# Analog_temperature_sensor.net
KiCad netlist of a schematic drawn in Altium Designer
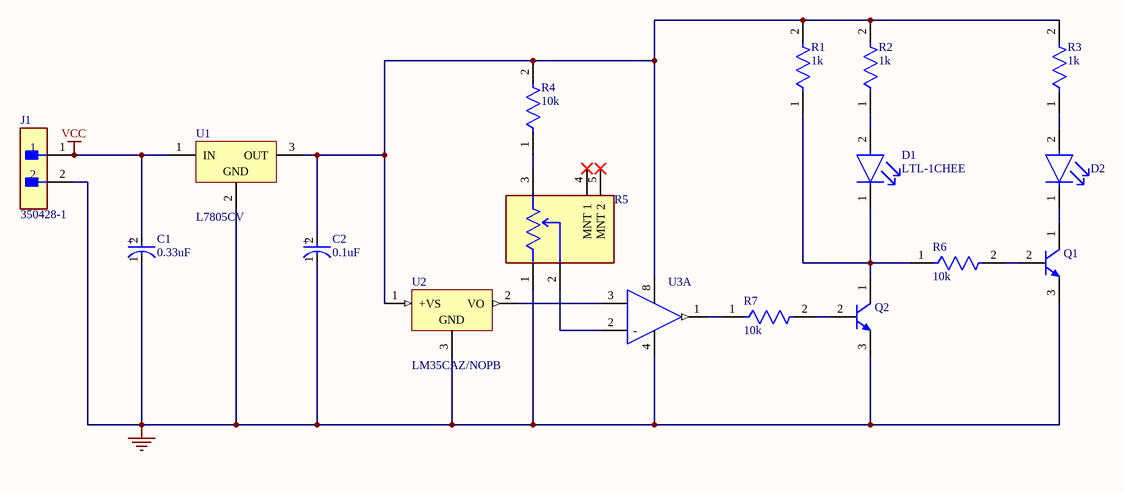
[diagram p0: Analog temperature sensor.SchDoc]

(export (version "E")
  (design (tool "Eeschema 10.0.6"))
  (components
    (comp (ref "C1")
      (value "0.33uF")
      (footprint "FP-RAD-TH-D_16_0_5-L_25_2-MFG")
      (description "Aluminum Electrolytic Capacitors (Radial Lead Type) 47uF ±20% 400V")
      (fields (field (name "VOLTAGE") "400V") (field (name "TOLERANCE") "20%"))
      (libsource (lib "Altium Content Vault") (part "203bc49f2ac43e59fd269a8c329ed05"))
    )
    (comp (ref "C2")
      (value "0.1uF")
      (footprint "FP-RAD-TH-D_16_0_5-L_25_2-MFG")
      (description "Aluminum Electrolytic Capacitors (Radial Lead Type) 47uF ±20% 400V")
      (fields (field (name "VOLTAGE") "400V") (field (name "TOLERANCE") "20%"))
      (libsource (lib "Altium Content Vault") (part "203bc49f2ac43e59fd269a8c329ed05"))
    )
    (comp (ref "D1")
      (value "LTL-1CHEE")
      (footprint "FP-LTL-1CHEE-MFG")
      (description "LED RED CLEAR T/H")
      (libsource (lib "Altium Content Vault") (part "8706943c75ba83719d021d2fdc84c58"))
    )
    (comp (ref "D2")
      (value "TLLG4400")
      (footprint "FP-6_544-5255_01-4-MFG")
      (description "TLLG4400 Led, Pcb, Green, 0.63MCD, 3MM, T-1, 7MA, 1.9V, 565NM, 25DEG, 20V, 20MW, -40")
      (libsource (lib "Altium Content Vault") (part "8706943c75ba83719d021d2fdc84c58"))
    )
    (comp (ref "J1")
      (value "350428-1")
      (footprint "FP-350428-1-MFG")
      (description "CONN HEADER VERT 2POS 6.35MM")
      (fields
        (field (name "OCTOPART") "https://octopart.com/350428-1-te+connectivity-46505355")
        (field (name "MANUFACTURER") "TE Connectivity")
      )
      (libsource (lib "Altium Content Vault") (part "3bc925449376181038e59eaffc5286c"))
    )
    (comp (ref "Q1")
      (value "BC547BRL1G")
      (footprint "ONSC-TO-92-3-29-11_AM_BL")
      (description "Amplifier Transistor, NPN Silicon, 3-Pin TO-92, Pb-Free, Tape and Reel")
      (fields (field (name "MANUFACTURER") "On Semiconductor"))
      (libsource (lib "Altium Content Vault") (part "ONSC-NPN-C1B2E3-3"))
    )
    (comp (ref "Q2")
      (value "BC547BRL1G")
      (footprint "ONSC-TO-92-3-29-11_AM_BL")
      (description "Amplifier Transistor, NPN Silicon, 3-Pin TO-92, Pb-Free, Tape and Reel")
      (fields (field (name "MANUFACTURER") "On Semiconductor"))
      (libsource (lib "Altium Content Vault") (part "ONSC-NPN-C1B2E3-3"))
    )
    (comp (ref "R1")
      (value "1k")
      (footprint "FP-CF14-MFG")
      (description "RES 7.5K OHM 1/4W 5% AXIAL")
      (fields (field (name "TOLERANCE") "5%"))
      (libsource (lib "Altium Content Vault") (part "1029c3af85768c4190bb7ad29bc67b5"))
    )
    (comp (ref "R2")
      (value "1k")
      (footprint "FP-CF14-MFG")
      (description "RES 7.5K OHM 1/4W 5% AXIAL")
      (fields (field (name "TOLERANCE") "5%"))
      (libsource (lib "Altium Content Vault") (part "1029c3af85768c4190bb7ad29bc67b5"))
    )
    (comp (ref "R3")
      (value "1k")
      (footprint "FP-CF14-MFG")
      (description "RES 7.5K OHM 1/4W 5% AXIAL")
      (fields (field (name "TOLERANCE") "5%"))
      (libsource (lib "Altium Content Vault") (part "1029c3af85768c4190bb7ad29bc67b5"))
    )
    (comp (ref "R4")
      (value "10k")
      (footprint "FP-CF14-MFG")
      (description "RES 7.5K OHM 1/4W 5% AXIAL")
      (fields (field (name "TOLERANCE") "5%"))
      (libsource (lib "Altium Content Vault") (part "1029c3af85768c4190bb7ad29bc67b5"))
    )
    (comp (ref "R5")
      (value "PTV09A-4225F-B103")
      (footprint "FP-PTV09A-4-MFG")
      (description "POT 10K OHM 1/20W CARBON LINEAR")
      (fields (field (name "TOLERANCE") "20%"))
      (libsource (lib "Altium Content Vault") (part "705d11b747745a787204d796a5f3d12"))
    )
    (comp (ref "R6")
      (value "10k")
      (footprint "FP-CF14-MFG")
      (description "RES 7.5K OHM 1/4W 5% AXIAL")
      (fields (field (name "TOLERANCE") "5%"))
      (libsource (lib "Altium Content Vault") (part "1029c3af85768c4190bb7ad29bc67b5"))
    )
    (comp (ref "R7")
      (value "10k")
      (footprint "FP-CF14-MFG")
      (description "RES 7.5K OHM 1/4W 5% AXIAL")
      (fields (field (name "TOLERANCE") "5%"))
      (libsource (lib "Altium Content Vault") (part "1029c3af85768c4190bb7ad29bc67b5"))
    )
    (comp (ref "U1")
      (value "L7805CV")
      (footprint "TO220")
      (description "Positive Voltage Regulator, 5V, 3-Pin TO-220")
      (libsource (lib "Altium Content Vault") (part "PM-REG-L4940-SIL3"))
    )
    (comp (ref "U2")
      (value "LM35CAZ/NOPB")
      (footprint "LP0003A")
      (description "Precision Centigrade Temperature Sensor, 3-pin TO-92, Pb-Free")
      (fields (field (name "MANUFACTURER") "Texas Instruments"))
      (libsource (lib "Altium Content Vault") (part "SEN-TEMP-LM34AH-3"))
    )
    (comp (ref "U3")
      (value "LM358DR")
      (footprint "FP-D0008A-MFG")
      (description "IC OPAMP GP 2 CIRCUIT 8SOIC")
      (libsource (lib "Altium Content Vault") (part "0afdfe5f461d2cdd85604ff8654be97"))
    )
  )
  (nets
    (net (code "1") (name "GND") (class "Default")
      (node (ref "C1") (pin "1") (pinfunction "C_1") (pintype "passive"))
      (node (ref "C2") (pin "1") (pinfunction "C_1") (pintype "passive"))
      (node (ref "J1") (pin "2") (pinfunction "2_2") (pintype "passive"))
      (node (ref "Q1") (pin "3") (pinfunction "E_3") (pintype "passive"))
      (node (ref "Q2") (pin "3") (pinfunction "E_3") (pintype "passive"))
      (node (ref "R5") (pin "1") (pinfunction "1_1") (pintype "passive"))
      (node (ref "U1") (pin "2") (pinfunction "GND_2") (pintype "power_in"))
      (node (ref "U2") (pin "3") (pinfunction "GND_3") (pintype "power_in"))
      (node (ref "U3") (pin "4") (pinfunction "V-_4") (pintype "power_in"))
    )
    (net (code "2") (name "Net-(C2-A)") (class "Default")
      (node (ref "C2") (pin "2") (pinfunction "A_2") (pintype "passive"))
      (node (ref "R1") (pin "2") (pinfunction "2_2") (pintype "passive"))
      (node (ref "R2") (pin "2") (pinfunction "2_2") (pintype "passive"))
      (node (ref "R3") (pin "2") (pinfunction "2_2") (pintype "passive"))
      (node (ref "R4") (pin "2") (pinfunction "2_2") (pintype "passive"))
      (node (ref "U1") (pin "3") (pinfunction "OUT_3") (pintype "power_in"))
      (node (ref "U2") (pin "1") (pinfunction "+VS_1") (pintype "input"))
      (node (ref "U3") (pin "8") (pinfunction "V+_8") (pintype "power_in"))
    )
    (net (code "3") (name "Net-(D1-A)") (class "Default")
      (node (ref "D1") (pin "2") (pinfunction "A_2") (pintype "passive"))
      (node (ref "R2") (pin "1") (pinfunction "1_1") (pintype "passive"))
    )
    (net (code "4") (name "Net-(D1-C)") (class "Default")
      (node (ref "D1") (pin "1") (pinfunction "C_1") (pintype "passive"))
      (node (ref "Q2") (pin "1") (pinfunction "C_1") (pintype "passive"))
      (node (ref "R1") (pin "1") (pinfunction "1_1") (pintype "passive"))
      (node (ref "R6") (pin "1") (pinfunction "1_1") (pintype "passive"))
    )
    (net (code "5") (name "Net-(D2-A)") (class "Default")
      (node (ref "D2") (pin "2") (pinfunction "A_2") (pintype "passive"))
      (node (ref "R3") (pin "1") (pinfunction "1_1") (pintype "passive"))
    )
    (net (code "6") (name "Net-(D2-C)") (class "Default")
      (node (ref "D2") (pin "1") (pinfunction "C_1") (pintype "passive"))
      (node (ref "Q1") (pin "1") (pinfunction "C_1") (pintype "passive"))
    )
    (net (code "7") (name "Net-(Q1-B)") (class "Default")
      (node (ref "Q1") (pin "2") (pinfunction "B_2") (pintype "passive"))
      (node (ref "R6") (pin "2") (pinfunction "2_2") (pintype "passive"))
    )
    (net (code "8") (name "Net-(Q2-B)") (class "Default")
      (node (ref "Q2") (pin "2") (pinfunction "B_2") (pintype "passive"))
      (node (ref "R7") (pin "2") (pinfunction "2_2") (pintype "passive"))
    )
    (net (code "9") (name "Net-(R4-Pad1)") (class "Default")
      (node (ref "R4") (pin "1") (pinfunction "1_1") (pintype "passive"))
      (node (ref "R5") (pin "3") (pinfunction "3_3") (pintype "passive"))
    )
    (net (code "10") (name "Net-(U2-VO)") (class "Default")
      (node (ref "U2") (pin "2") (pinfunction "VO_2") (pintype "output"))
      (node (ref "U3") (pin "3") (pinfunction "IN1+_3") (pintype "tri_state"))
    )
    (net (code "11") (name "Net-(U3A-1OUT)") (class "Default")
      (node (ref "R7") (pin "1") (pinfunction "1_1") (pintype "passive"))
      (node (ref "U3") (pin "1") (pinfunction "1OUT_1") (pintype "output"))
    )
    (net (code "12") (name "Net-(U3A-IN1-)") (class "Default")
      (node (ref "R5") (pin "2") (pinfunction "2_2") (pintype "passive"))
      (node (ref "U3") (pin "2") (pinfunction "IN1-_2") (pintype "tri_state"))
    )
    (net (code "13") (name "VCC") (class "Default")
      (node (ref "C1") (pin "2") (pinfunction "A_2") (pintype "passive"))
      (node (ref "J1") (pin "1") (pinfunction "1_1") (pintype "passive"))
      (node (ref "U1") (pin "1") (pinfunction "IN_1") (pintype "power_in"))
    )
    (net (code "14") (name "unconnected-(R5-MNT_1-Pad4)") (class "Default")
      (node (ref "R5") (pin "4") (pinfunction "MNT_1_4") (pintype "passive+no_connect"))
    )
    (net (code "15") (name "unconnected-(R5-MNT_2-Pad5)") (class "Default")
      (node (ref "R5") (pin "5") (pinfunction "MNT_2_5") (pintype "passive+no_connect"))
    )
  )
)
